# EPS_Interface.net
KiCad netlist of a schematic drawn in Altium Designer
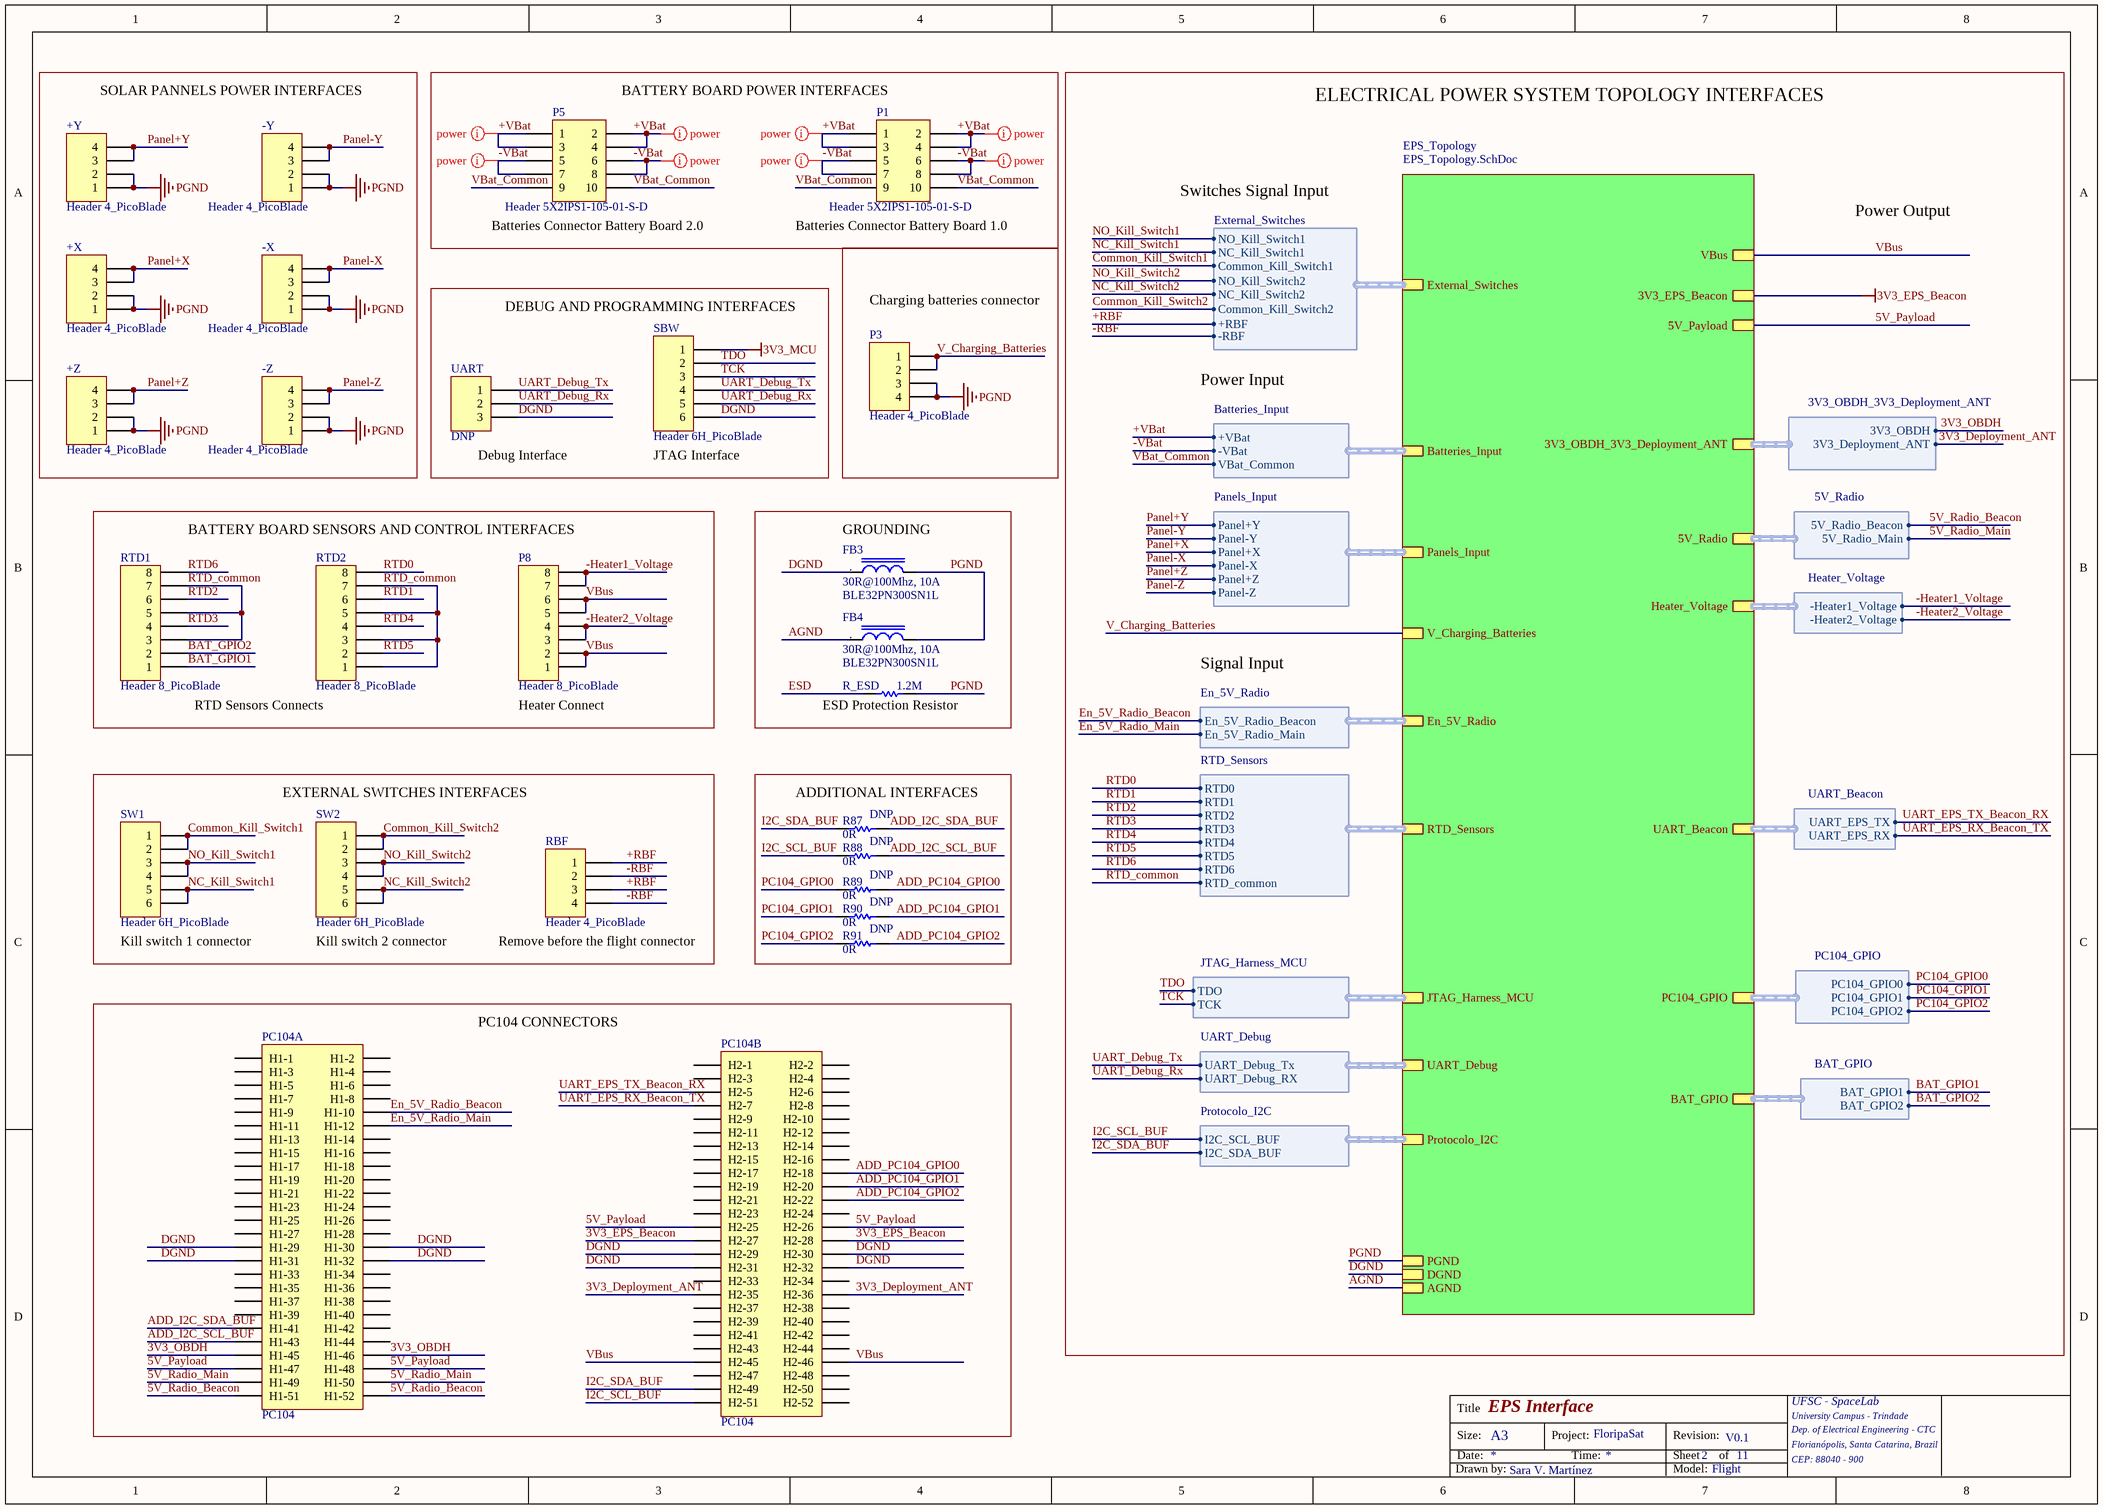
[diagram p0: EPS_Interface.SchDoc]

(export (version "E")
  (design (tool "Eeschema 10.0.6"))
  (components
    (comp (ref "+X")
      (value "Header 4_PicoBlade")
      (footprint "HDR4 PicoBlade")
      (description "Header, 4-Pin")
      (fields
        (field (name "PARTNUMBER") "53398-0471")
        (field (name "MANUFACTURER") "Molex")
        (field (name "PUBLISHER") "Altium Limited")
      )
      (libsource (lib "PCB_Project_FlightModel_EPS") (part "Header 4_PicoBlade"))
    )
    (comp (ref "+Y")
      (value "Header 4_PicoBlade")
      (footprint "HDR4 PicoBlade")
      (description "Header, 4-Pin")
      (fields
        (field (name "PARTNUMBER") "53398-0471")
        (field (name "MANUFACTURER") "Molex")
        (field (name "PUBLISHER") "Altium Limited")
      )
      (libsource (lib "PCB_Project_FlightModel_EPS") (part "Header 4_PicoBlade"))
    )
    (comp (ref "+Z")
      (value "Header 4_PicoBlade")
      (footprint "HDR4 PicoBlade")
      (description "Header, 4-Pin")
      (fields
        (field (name "PARTNUMBER") "53398-0471")
        (field (name "MANUFACTURER") "Molex")
        (field (name "PUBLISHER") "Altium Limited")
      )
      (libsource (lib "PCB_Project_FlightModel_EPS") (part "Header 4_PicoBlade"))
    )
    (comp (ref "-X")
      (value "Header 4_PicoBlade")
      (footprint "HDR4 PicoBlade")
      (description "Header, 4-Pin")
      (fields
        (field (name "PARTNUMBER") "53398-0471")
        (field (name "MANUFACTURER") "Molex")
        (field (name "PUBLISHER") "Altium Limited")
      )
      (libsource (lib "PCB_Project_FlightModel_EPS") (part "Header 4_PicoBlade"))
    )
    (comp (ref "-Y")
      (value "Header 4_PicoBlade")
      (footprint "HDR4 PicoBlade")
      (description "Header, 4-Pin")
      (fields
        (field (name "PARTNUMBER") "53398-0471")
        (field (name "MANUFACTURER") "Molex")
        (field (name "PUBLISHER") "Altium Limited")
      )
      (libsource (lib "PCB_Project_FlightModel_EPS") (part "Header 4_PicoBlade"))
    )
    (comp (ref "-Z")
      (value "Header 4_PicoBlade")
      (footprint "HDR4 PicoBlade")
      (description "Header, 4-Pin")
      (fields
        (field (name "PARTNUMBER") "53398-0471")
        (field (name "MANUFACTURER") "Molex")
        (field (name "PUBLISHER") "Altium Limited")
      )
      (libsource (lib "PCB_Project_FlightModel_EPS") (part "Header 4_PicoBlade"))
    )
    (comp (ref "FB3")
      (value "30R@100Mhz, 10A")
      (footprint "IND1210")
      (description "Ferrite Bead 30 OHM 10A 100MHz")
      (fields
        (field (name "PARTNUMBER") "BLE32PN300SN1L")
        (field (name "MANUFACTURER") "Murata")
        (field (name "MANUFACTURER PART NUMBER") "BLE32PN300SN1L")
      )
      (libsource (lib "PCB_Project_FlightModel_EPS") (part "FB_30R_10A_100MHz_1210"))
    )
    (comp (ref "FB4")
      (value "30R@100Mhz, 10A")
      (footprint "IND1210")
      (description "Ferrite Bead 30 OHM 10A 100MHz")
      (fields
        (field (name "PARTNUMBER") "BLE32PN300SN1L")
        (field (name "MANUFACTURER") "Murata")
        (field (name "MANUFACTURER PART NUMBER") "BLE32PN300SN1L")
      )
      (libsource (lib "PCB_Project_FlightModel_EPS") (part "FB_30R_10A_100MHz_1210"))
    )
    (comp (ref "P1")
      (value "Header 5X2IPS1-105-01-S-D")
      (footprint "IPS1-105-01-S-D")
      (description "10 Position Receptacle Connector 0.100\" (2.54mm)")
      (fields
        (field (name "PARTNUMBER") "IPS1-105-01-S-D")
        (field (name "MANUFACTURER") "Samtec")
        (field (name "PUBLISHER") "Altium Limited")
      )
      (libsource (lib "PCB_Project_FlightModel_EPS") (part "Header 5X2H_IPS1-105-01-S-D-VS"))
    )
    (comp (ref "P3")
      (value "Header 4_PicoBlade")
      (footprint "HDR4 PicoBlade")
      (description "Header, 4-Pin")
      (fields
        (field (name "PARTNUMBER") "53398-0471")
        (field (name "MANUFACTURER") "Molex")
        (field (name "PUBLISHER") "Altium Limited")
      )
      (libsource (lib "") (part "Header 4_PicoBlade_1"))
    )
    (comp (ref "P5")
      (value "Header 5X2IPS1-105-01-S-D")
      (footprint "IPS1-105-01-S-D")
      (description "10 Position Receptacle Connector 0.100\" (2.54mm)")
      (fields
        (field (name "PARTNUMBER") "IPS1-105-01-S-D")
        (field (name "MANUFACTURER") "Samtec")
        (field (name "PUBLISHER") "Altium Limited")
      )
      (libsource (lib "PCB_Project_FlightModel_EPS") (part "Header 5X2H_IPS1-105-01-S-D-VS"))
    )
    (comp (ref "P8")
      (value "Header 8_PicoBlade")
      (footprint "HDR8 PicoBlade")
      (description "Header, 8-Pin")
      (fields
        (field (name "PARTNUMBER") "53261-0871")
        (field (name "MANUFACTURER") "Molex")
        (field (name "PUBLISHER") "Altium Limited")
      )
      (libsource (lib "PCB_Project_FlightModel_EPS") (part "Header 8_PicoBlade"))
    )
    (comp (ref "PC104")
      (value "PC104")
      (footprint "PC104")
      (fields (field (name "PARTNUMBER") "SSW-126-01-G-D") (field (name "MANUFACTURER") "Samtec"))
      (libsource (lib "") (part "PC104_1"))
    )
    (comp (ref "R87")
      (value "0R")
      (footprint "0805")
      (description "RES 0R OHM 1/8W JUMPER 0805")
      (fields (field (name "PARTNUMBER") "CRCW08050000Z0EA") (field (name "MANUFACTURER") "Vishay"))
      (libsource (lib "PCB_Project_FlightModel_EPS") (part "R0R_JUMPER_1/8W_0805"))
    )
    (comp (ref "R88")
      (value "0R")
      (footprint "0805")
      (description "RES 0R OHM 1/8W JUMPER 0805")
      (fields (field (name "PARTNUMBER") "CRCW08050000Z0EA") (field (name "MANUFACTURER") "Vishay"))
      (libsource (lib "PCB_Project_FlightModel_EPS") (part "R0R_JUMPER_1/8W_0805"))
    )
    (comp (ref "R89")
      (value "0R")
      (footprint "0805")
      (description "RES 0R OHM 1/8W JUMPER 0805")
      (fields (field (name "PARTNUMBER") "CRCW08050000Z0EA") (field (name "MANUFACTURER") "Vishay"))
      (libsource (lib "PCB_Project_FlightModel_EPS") (part "R0R_JUMPER_1/8W_0805"))
    )
    (comp (ref "R90")
      (value "0R")
      (footprint "0805")
      (description "RES 0R OHM 1/8W JUMPER 0805")
      (fields (field (name "PARTNUMBER") "CRCW08050000Z0EA") (field (name "MANUFACTURER") "Vishay"))
      (libsource (lib "PCB_Project_FlightModel_EPS") (part "R0R_JUMPER_1/8W_0805"))
    )
    (comp (ref "R91")
      (value "0R")
      (footprint "0805")
      (description "RES 0R OHM 1/8W JUMPER 0805")
      (fields (field (name "PARTNUMBER") "CRCW08050000Z0EA") (field (name "MANUFACTURER") "Vishay"))
      (libsource (lib "PCB_Project_FlightModel_EPS") (part "R0R_JUMPER_1/8W_0805"))
    )
    (comp (ref "RBF")
      (value "Header 4_PicoBlade")
      (footprint "HDR4 PicoBlade")
      (description "Header, 4-Pin")
      (fields
        (field (name "PARTNUMBER") "53398-0471")
        (field (name "MANUFACTURER") "Molex")
        (field (name "PUBLISHER") "Altium Limited")
      )
      (libsource (lib "") (part "Header 4_PicoBlade_1"))
    )
    (comp (ref "RTD1")
      (value "Header 8_PicoBlade")
      (footprint "HDR8 PicoBlade")
      (description "Header, 8-Pin")
      (fields
        (field (name "PARTNUMBER") "53261-0871")
        (field (name "MANUFACTURER") "Molex")
        (field (name "PUBLISHER") "Altium Limited")
      )
      (libsource (lib "PCB_Project_FlightModel_EPS") (part "Header 8_PicoBlade"))
    )
    (comp (ref "RTD2")
      (value "Header 8_PicoBlade")
      (footprint "HDR8 PicoBlade")
      (description "Header, 8-Pin")
      (fields
        (field (name "PARTNUMBER") "53261-0871")
        (field (name "MANUFACTURER") "Molex")
        (field (name "PUBLISHER") "Altium Limited")
      )
      (libsource (lib "PCB_Project_FlightModel_EPS") (part "Header 8_PicoBlade"))
    )
    (comp (ref "R_ESD")
      (value "1.2M")
      (footprint "0805")
      (description "RES 1200K OHM 1/8W 0.1% 0805")
      (fields (field (name "PARTNUMBER") "RG2012P-125-B-T5") (field (name "MANUFACTURER") "Susumu"))
      (libsource (lib "PCB_Project_FlightModel_EPS") (part "R1200k_1%_1/8W_0805"))
    )
    (comp (ref "SBW")
      (value "Header 6H_PicoBlade")
      (footprint "HDR6 PicoBlade")
      (description "Header, 6-Pin, Right Angle")
      (fields
        (field (name "PARTNUMBER") "53398-0671")
        (field (name "MANUFACTURER") "Molex")
        (field (name "PUBLISHER") "Altium Limited")
      )
      (libsource (lib "PCB_Project_FlightModel_EPS") (part "Header 6H_PicoBlade"))
    )
    (comp (ref "SW1")
      (value "Header 6H_PicoBlade")
      (footprint "HDR6 PicoBlade")
      (description "Header, 6-Pin, Right Angle")
      (fields
        (field (name "PARTNUMBER") "53398-0671")
        (field (name "MANUFACTURER") "Molex")
        (field (name "PUBLISHER") "Altium Limited")
      )
      (libsource (lib "PCB_Project_FlightModel_EPS") (part "Header 6H_PicoBlade"))
    )
    (comp (ref "SW2")
      (value "Header 6H_PicoBlade")
      (footprint "HDR6 PicoBlade")
      (description "Header, 6-Pin, Right Angle")
      (fields
        (field (name "PARTNUMBER") "53398-0671")
        (field (name "MANUFACTURER") "Molex")
        (field (name "PUBLISHER") "Altium Limited")
      )
      (libsource (lib "PCB_Project_FlightModel_EPS") (part "Header 6H_PicoBlade"))
    )
    (comp (ref "UART")
      (value "DNP")
      (footprint "HDR 1X3")
      (description "Header, 3-Pin, Right Angle")
      (fields
        (field (name "PARTNUMBER") "4-103327-5")
        (field (name "MANUFACTURER") "TE Connectivity AMP")
        (field (name "PUBLISHER") "Altium Limited")
      )
      (libsource (lib "PCB_Project_FlightModel_EPS") (part "Header 3H"))
    )
  )
  (nets
    (net (code "15") (name "/+RBF") (class "Default")
      (node (ref "RBF") (pin "1") (pinfunction "1_1") (pintype "passive"))
      (node (ref "RBF") (pin "3") (pinfunction "3_3") (pintype "passive"))
    )
    (net (code "16") (name "/+VBat") (class "Default")
      (node (ref "P1") (pin "1") (pinfunction "1_1") (pintype "passive"))
      (node (ref "P1") (pin "2") (pinfunction "2_2") (pintype "passive"))
      (node (ref "P1") (pin "3") (pinfunction "3_3") (pintype "passive"))
      (node (ref "P1") (pin "4") (pinfunction "4_4") (pintype "passive"))
      (node (ref "P5") (pin "1") (pinfunction "1_1") (pintype "passive"))
      (node (ref "P5") (pin "2") (pinfunction "2_2") (pintype "passive"))
      (node (ref "P5") (pin "3") (pinfunction "3_3") (pintype "passive"))
      (node (ref "P5") (pin "4") (pinfunction "4_4") (pintype "passive"))
    )
    (net (code "17") (name "/-Heater1_Voltage") (class "Default")
      (node (ref "P8") (pin "7") (pinfunction "7_7") (pintype "passive"))
      (node (ref "P8") (pin "8") (pinfunction "8_8") (pintype "passive"))
    )
    (net (code "18") (name "/-Heater2_Voltage") (class "Default")
      (node (ref "P8") (pin "3") (pinfunction "3_3") (pintype "passive"))
      (node (ref "P8") (pin "4") (pinfunction "4_4") (pintype "passive"))
    )
    (net (code "19") (name "/-RBF") (class "Default")
      (node (ref "RBF") (pin "2") (pinfunction "2_2") (pintype "passive"))
      (node (ref "RBF") (pin "4") (pinfunction "4_4") (pintype "passive"))
    )
    (net (code "20") (name "/-VBat") (class "Default")
      (node (ref "P1") (pin "5") (pinfunction "5_5") (pintype "passive"))
      (node (ref "P1") (pin "6") (pinfunction "6_6") (pintype "passive"))
      (node (ref "P1") (pin "7") (pinfunction "7_7") (pintype "passive"))
      (node (ref "P1") (pin "8") (pinfunction "8_8") (pintype "passive"))
      (node (ref "P5") (pin "5") (pinfunction "5_5") (pintype "passive"))
      (node (ref "P5") (pin "6") (pinfunction "6_6") (pintype "passive"))
      (node (ref "P5") (pin "7") (pinfunction "7_7") (pintype "passive"))
      (node (ref "P5") (pin "8") (pinfunction "8_8") (pintype "passive"))
    )
    (net (code "21") (name "/3V3_Deployment_ANT") (class "Default")
      (node (ref "PC104") (pin "H2-35") (pinfunction "H2-35_H2-35") (pintype "passive"))
      (node (ref "PC104") (pin "H2-36") (pinfunction "H2-36_H2-36") (pintype "passive"))
    )
    (net (code "22") (name "/3V3_OBDH") (class "Default")
      (node (ref "PC104") (pin "H1-45") (pinfunction "H1-45_H1-45") (pintype "passive"))
      (node (ref "PC104") (pin "H1-46") (pinfunction "H1-46_H1-46") (pintype "passive"))
    )
    (net (code "23") (name "/5V_Payload") (class "Default")
      (node (ref "PC104") (pin "H1-47") (pinfunction "H1-47_H1-47") (pintype "passive"))
      (node (ref "PC104") (pin "H1-48") (pinfunction "H1-48_H1-48") (pintype "passive"))
      (node (ref "PC104") (pin "H2-25") (pinfunction "H2-25_H2-25") (pintype "passive"))
      (node (ref "PC104") (pin "H2-26") (pinfunction "H2-26_H2-26") (pintype "passive"))
    )
    (net (code "24") (name "/5V_Radio_Beacon") (class "Default")
      (node (ref "PC104") (pin "H1-51") (pinfunction "H1-51_H1-51") (pintype "passive"))
      (node (ref "PC104") (pin "H1-52") (pinfunction "H1-52_H1-52") (pintype "passive"))
    )
    (net (code "25") (name "/5V_Radio_Main") (class "Default")
      (node (ref "PC104") (pin "H1-49") (pinfunction "H1-49_H1-49") (pintype "passive"))
      (node (ref "PC104") (pin "H1-50") (pinfunction "H1-50_H1-50") (pintype "passive"))
    )
    (net (code "26") (name "/ADD_I2C_SCL_BUF") (class "Default")
      (node (ref "PC104") (pin "H1-43") (pinfunction "H1-43_H1-43") (pintype "passive"))
      (node (ref "R88") (pin "1") (pinfunction "1_1") (pintype "passive"))
    )
    (net (code "27") (name "/ADD_I2C_SDA_BUF") (class "Default")
      (node (ref "PC104") (pin "H1-41") (pinfunction "H1-41_H1-41") (pintype "passive"))
      (node (ref "R87") (pin "1") (pinfunction "1_1") (pintype "passive"))
    )
    (net (code "28") (name "/ADD_PC104_GPIO0") (class "Default")
      (node (ref "PC104") (pin "H2-18") (pinfunction "H2-18_H2-18") (pintype "passive"))
      (node (ref "R89") (pin "1") (pinfunction "1_1") (pintype "passive"))
    )
    (net (code "29") (name "/ADD_PC104_GPIO1") (class "Default")
      (node (ref "PC104") (pin "H2-20") (pinfunction "H2-20_H2-20") (pintype "passive"))
      (node (ref "R90") (pin "1") (pinfunction "1_1") (pintype "passive"))
    )
    (net (code "30") (name "/ADD_PC104_GPIO2") (class "Default")
      (node (ref "PC104") (pin "H2-22") (pinfunction "H2-22_H2-22") (pintype "passive"))
      (node (ref "R91") (pin "1") (pinfunction "1_1") (pintype "passive"))
    )
    (net (code "31") (name "/AGND") (class "Default")
      (node (ref "FB4") (pin "1") (pinfunction "1_1") (pintype "passive"))
    )
    (net (code "32") (name "/BAT_GPIO1") (class "Default")
      (node (ref "RTD1") (pin "1") (pinfunction "1_1") (pintype "passive"))
    )
    (net (code "33") (name "/BAT_GPIO2") (class "Default")
      (node (ref "RTD1") (pin "2") (pinfunction "2_2") (pintype "passive"))
    )
    (net (code "34") (name "/Common_Kill_Switch1") (class "Default")
      (node (ref "SW1") (pin "1") (pinfunction "1_1") (pintype "passive"))
      (node (ref "SW1") (pin "2") (pinfunction "2_2") (pintype "passive"))
    )
    (net (code "35") (name "/Common_Kill_Switch2") (class "Default")
      (node (ref "SW2") (pin "1") (pinfunction "1_1") (pintype "passive"))
      (node (ref "SW2") (pin "2") (pinfunction "2_2") (pintype "passive"))
    )
    (net (code "36") (name "/DGND") (class "Default")
      (node (ref "FB3") (pin "1") (pinfunction "1_1") (pintype "passive"))
      (node (ref "PC104") (pin "H1-29") (pinfunction "H1-29_H1-29") (pintype "passive"))
      (node (ref "PC104") (pin "H1-30") (pinfunction "H1-30_H1-30") (pintype "passive"))
      (node (ref "PC104") (pin "H1-31") (pinfunction "H1-31_H1-31") (pintype "passive"))
      (node (ref "PC104") (pin "H1-32") (pinfunction "H1-32_H1-32") (pintype "passive"))
      (node (ref "PC104") (pin "H2-29") (pinfunction "H2-29_H2-29") (pintype "passive"))
      (node (ref "PC104") (pin "H2-30") (pinfunction "H2-30_H2-30") (pintype "passive"))
      (node (ref "PC104") (pin "H2-31") (pinfunction "H2-31_H2-31") (pintype "passive"))
      (node (ref "PC104") (pin "H2-32") (pinfunction "H2-32_H2-32") (pintype "passive"))
      (node (ref "SBW") (pin "6") (pinfunction "6_6") (pintype "passive"))
      (node (ref "UART") (pin "3") (pinfunction "3_3") (pintype "passive"))
    )
    (net (code "37") (name "/ESD") (class "Default")
      (node (ref "R_ESD") (pin "2") (pinfunction "2_2") (pintype "passive"))
    )
    (net (code "38") (name "/En_5V_Radio_Beacon") (class "Default")
      (node (ref "PC104") (pin "H1-10") (pinfunction "H1-10_H1-10") (pintype "passive"))
    )
    (net (code "39") (name "/En_5V_Radio_Main") (class "Default")
      (node (ref "PC104") (pin "H1-12") (pinfunction "H1-12_H1-12") (pintype "passive"))
    )
    (net (code "40") (name "/I2C_SCL_BUF") (class "Default")
      (node (ref "PC104") (pin "H2-51") (pinfunction "H2-51_H2-51") (pintype "passive"))
      (node (ref "R88") (pin "2") (pinfunction "2_2") (pintype "passive"))
    )
    (net (code "41") (name "/I2C_SDA_BUF") (class "Default")
      (node (ref "PC104") (pin "H2-49") (pinfunction "H2-49_H2-49") (pintype "passive"))
      (node (ref "R87") (pin "2") (pinfunction "2_2") (pintype "passive"))
    )
    (net (code "42") (name "/NC_Kill_Switch1") (class "Default")
      (node (ref "SW1") (pin "5") (pinfunction "5_5") (pintype "passive"))
      (node (ref "SW1") (pin "6") (pinfunction "6_6") (pintype "passive"))
    )
    (net (code "43") (name "/NC_Kill_Switch2") (class "Default")
      (node (ref "SW2") (pin "5") (pinfunction "5_5") (pintype "passive"))
      (node (ref "SW2") (pin "6") (pinfunction "6_6") (pintype "passive"))
    )
    (net (code "44") (name "/NO_Kill_Switch1") (class "Default")
      (node (ref "SW1") (pin "3") (pinfunction "3_3") (pintype "passive"))
      (node (ref "SW1") (pin "4") (pinfunction "4_4") (pintype "passive"))
    )
    (net (code "45") (name "/NO_Kill_Switch2") (class "Default")
      (node (ref "SW2") (pin "3") (pinfunction "3_3") (pintype "passive"))
      (node (ref "SW2") (pin "4") (pinfunction "4_4") (pintype "passive"))
    )
    (net (code "46") (name "/PC104_GPIO0") (class "Default")
      (node (ref "R89") (pin "2") (pinfunction "2_2") (pintype "passive"))
    )
    (net (code "47") (name "/PC104_GPIO1") (class "Default")
      (node (ref "R90") (pin "2") (pinfunction "2_2") (pintype "passive"))
    )
    (net (code "48") (name "/PC104_GPIO2") (class "Default")
      (node (ref "R91") (pin "2") (pinfunction "2_2") (pintype "passive"))
    )
    (net (code "49") (name "/Panel+X") (class "Default")
      (node (ref "+X") (pin "3") (pinfunction "3_3") (pintype "passive"))
      (node (ref "+X") (pin "4") (pinfunction "4_4") (pintype "passive"))
    )
    (net (code "50") (name "/Panel+Y") (class "Default")
      (node (ref "+Y") (pin "3") (pinfunction "3_3") (pintype "passive"))
      (node (ref "+Y") (pin "4") (pinfunction "4_4") (pintype "passive"))
    )
    (net (code "51") (name "/Panel+Z") (class "Default")
      (node (ref "+Z") (pin "3") (pinfunction "3_3") (pintype "passive"))
      (node (ref "+Z") (pin "4") (pinfunction "4_4") (pintype "passive"))
    )
    (net (code "52") (name "/Panel-X") (class "Default")
      (node (ref "-X") (pin "3") (pinfunction "3_3") (pintype "passive"))
      (node (ref "-X") (pin "4") (pinfunction "4_4") (pintype "passive"))
    )
    (net (code "53") (name "/Panel-Y") (class "Default")
      (node (ref "-Y") (pin "3") (pinfunction "3_3") (pintype "passive"))
      (node (ref "-Y") (pin "4") (pinfunction "4_4") (pintype "passive"))
    )
    (net (code "54") (name "/Panel-Z") (class "Default")
      (node (ref "-Z") (pin "3") (pinfunction "3_3") (pintype "passive"))
      (node (ref "-Z") (pin "4") (pinfunction "4_4") (pintype "passive"))
    )
    (net (code "55") (name "/RTD0") (class "Default")
      (node (ref "RTD2") (pin "8") (pinfunction "8_8") (pintype "passive"))
    )
    (net (code "56") (name "/RTD1") (class "Default")
      (node (ref "RTD2") (pin "6") (pinfunction "6_6") (pintype "passive"))
    )
    (net (code "57") (name "/RTD2") (class "Default")
      (node (ref "RTD1") (pin "6") (pinfunction "6_6") (pintype "passive"))
    )
    (net (code "58") (name "/RTD3") (class "Default")
      (node (ref "RTD1") (pin "4") (pinfunction "4_4") (pintype "passive"))
    )
    (net (code "59") (name "/RTD4") (class "Default")
      (node (ref "RTD2") (pin "4") (pinfunction "4_4") (pintype "passive"))
    )
    (net (code "60") (name "/RTD5") (class "Default")
      (node (ref "RTD2") (pin "2") (pinfunction "2_2") (pintype "passive"))
    )
    (net (code "61") (name "/RTD6") (class "Default")
      (node (ref "RTD1") (pin "8") (pinfunction "8_8") (pintype "passive"))
    )
    (net (code "62") (name "/RTD_common") (class "Default")
      (node (ref "RTD1") (pin "3") (pinfunction "3_3") (pintype "passive"))
      (node (ref "RTD1") (pin "5") (pinfunction "5_5") (pintype "passive"))
      (node (ref "RTD1") (pin "7") (pinfunction "7_7") (pintype "passive"))
      (node (ref "RTD2") (pin "1") (pinfunction "1_1") (pintype "passive"))
      (node (ref "RTD2") (pin "3") (pinfunction "3_3") (pintype "passive"))
      (node (ref "RTD2") (pin "5") (pinfunction "5_5") (pintype "passive"))
      (node (ref "RTD2") (pin "7") (pinfunction "7_7") (pintype "passive"))
    )
    (net (code "63") (name "/TCK") (class "Default")
      (node (ref "SBW") (pin "3") (pinfunction "3_3") (pintype "passive"))
    )
    (net (code "64") (name "/TDO") (class "Default")
      (node (ref "SBW") (pin "2") (pinfunction "2_2") (pintype "passive"))
    )
    (net (code "65") (name "/UART_Debug_Rx") (class "Default")
      (node (ref "SBW") (pin "5") (pinfunction "5_5") (pintype "passive"))
      (node (ref "UART") (pin "2") (pinfunction "2_2") (pintype "passive"))
    )
    (net (code "66") (name "/UART_Debug_Tx") (class "Default")
      (node (ref "SBW") (pin "4") (pinfunction "4_4") (pintype "passive"))
      (node (ref "UART") (pin "1") (pinfunction "1_1") (pintype "passive"))
    )
    (net (code "67") (name "/UART_EPS_RX_Beacon_TX") (class "Default")
      (node (ref "PC104") (pin "H2-7") (pinfunction "H2-7_H2-7") (pintype "passive"))
    )
    (net (code "68") (name "/UART_EPS_TX_Beacon_RX") (class "Default")
      (node (ref "PC104") (pin "H2-5") (pinfunction "H2-5_H2-5") (pintype "passive"))
    )
    (net (code "69") (name "/VBat_Common") (class "Default")
      (node (ref "P1") (pin "10") (pinfunction "10_10") (pintype "passive"))
      (node (ref "P1") (pin "9") (pinfunction "9_9") (pintype "passive"))
      (node (ref "P5") (pin "10") (pinfunction "10_10") (pintype "passive"))
      (node (ref "P5") (pin "9") (pinfunction "9_9") (pintype "passive"))
    )
    (net (code "70") (name "/VBus") (class "Default")
      (node (ref "P8") (pin "1") (pinfunction "1_1") (pintype "passive"))
      (node (ref "P8") (pin "2") (pinfunction "2_2") (pintype "passive"))
      (node (ref "P8") (pin "5") (pinfunction "5_5") (pintype "passive"))
      (node (ref "P8") (pin "6") (pinfunction "6_6") (pintype "passive"))
      (node (ref "PC104") (pin "H2-45") (pinfunction "H2-45_H2-45") (pintype "passive"))
      (node (ref "PC104") (pin "H2-46") (pinfunction "H2-46_H2-46") (pintype "passive"))
    )
    (net (code "71") (name "/V_Charging_Batteries") (class "Default")
      (node (ref "P3") (pin "1") (pinfunction "1_1") (pintype "passive"))
      (node (ref "P3") (pin "2") (pinfunction "2_2") (pintype "passive"))
    )
    (net (code "86") (name "3V3_EPS_Beacon") (class "Default")
      (node (ref "PC104") (pin "H2-27") (pinfunction "H2-27_H2-27") (pintype "passive"))
      (node (ref "PC104") (pin "H2-28") (pinfunction "H2-28_H2-28") (pintype "passive"))
    )
    (net (code "87") (name "3V3_MCU") (class "Default")
      (node (ref "SBW") (pin "1") (pinfunction "1_1") (pintype "passive"))
    )
    (net (code "88") (name "PGND") (class "Default")
      (node (ref "+X") (pin "1") (pinfunction "1_1") (pintype "passive"))
      (node (ref "+X") (pin "2") (pinfunction "2_2") (pintype "passive"))
      (node (ref "+Y") (pin "1") (pinfunction "1_1") (pintype "passive"))
      (node (ref "+Y") (pin "2") (pinfunction "2_2") (pintype "passive"))
      (node (ref "+Z") (pin "1") (pinfunction "1_1") (pintype "passive"))
      (node (ref "+Z") (pin "2") (pinfunction "2_2") (pintype "passive"))
      (node (ref "-X") (pin "1") (pinfunction "1_1") (pintype "passive"))
      (node (ref "-X") (pin "2") (pinfunction "2_2") (pintype "passive"))
      (node (ref "-Y") (pin "1") (pinfunction "1_1") (pintype "passive"))
      (node (ref "-Y") (pin "2") (pinfunction "2_2") (pintype "passive"))
      (node (ref "-Z") (pin "1") (pinfunction "1_1") (pintype "passive"))
      (node (ref "-Z") (pin "2") (pinfunction "2_2") (pintype "passive"))
      (node (ref "FB3") (pin "2") (pinfunction "2_2") (pintype "passive"))
      (node (ref "FB4") (pin "2") (pinfunction "2_2") (pintype "passive"))
      (node (ref "P3") (pin "3") (pinfunction "3_3") (pintype "passive"))
      (node (ref "P3") (pin "4") (pinfunction "4_4") (pintype "passive"))
      (node (ref "R_ESD") (pin "1") (pinfunction "1_1") (pintype "passive"))
    )
    (net (code "89") (name "unconnected-(PC104-PadH1-1)") (class "Default")
      (node (ref "PC104") (pin "H1-1") (pinfunction "H1-1_H1-1") (pintype "passive"))
    )
    (net (code "90") (name "unconnected-(PC104-PadH1-2)") (class "Default")
      (node (ref "PC104") (pin "H1-2") (pinfunction "H1-2_H1-2") (pintype "passive"))
    )
    (net (code "91") (name "unconnected-(PC104-PadH1-3)") (class "Default")
      (node (ref "PC104") (pin "H1-3") (pinfunction "H1-3_H1-3") (pintype "passive"))
    )
    (net (code "92") (name "unconnected-(PC104-PadH1-4)") (class "Default")
      (node (ref "PC104") (pin "H1-4") (pinfunction "H1-4_H1-4") (pintype "passive"))
    )
    (net (code "93") (name "unconnected-(PC104-PadH1-5)") (class "Default")
      (node (ref "PC104") (pin "H1-5") (pinfunction "H1-5_H1-5") (pintype "passive"))
    )
    (net (code "94") (name "unconnected-(PC104-PadH1-6)") (class "Default")
      (node (ref "PC104") (pin "H1-6") (pinfunction "H1-6_H1-6") (pintype "passive"))
    )
    (net (code "95") (name "unconnected-(PC104-PadH1-7)") (class "Default")
      (node (ref "PC104") (pin "H1-7") (pinfunction "H1-7_H1-7") (pintype "passive"))
    )
    (net (code "96") (name "unconnected-(PC104-PadH1-8)") (class "Default")
      (node (ref "PC104") (pin "H1-8") (pinfunction "H1-8_H1-8") (pintype "passive"))
    )
    (net (code "97") (name "unconnected-(PC104-PadH1-9)") (class "Default")
      (node (ref "PC104") (pin "H1-9") (pinfunction "H1-9_H1-9") (pintype "passive"))
    )
    (net (code "98") (name "unconnected-(PC104-PadH1-11)") (class "Default")
      (node (ref "PC104") (pin "H1-11") (pinfunction "H1-11_H1-11") (pintype "passive"))
    )
    (net (code "99") (name "unconnected-(PC104-PadH1-13)") (class "Default")
      (node (ref "PC104") (pin "H1-13") (pinfunction "H1-13_H1-13") (pintype "passive"))
    )
    (net (code "100") (name "unconnected-(PC104-PadH1-14)") (class "Default")
      (node (ref "PC104") (pin "H1-14") (pinfunction "H1-14_H1-14") (pintype "passive"))
    )
    (net (code "101") (name "unconnected-(PC104-PadH1-15)") (class "Default")
      (node (ref "PC104") (pin "H1-15") (pinfunction "H1-15_H1-15") (pintype "passive"))
    )
    (net (code "102") (name "unconnected-(PC104-PadH1-16)") (class "Default")
      (node (ref "PC104") (pin "H1-16") (pinfunction "H1-16_H1-16") (pintype "passive"))
    )
    (net (code "103") (name "unconnected-(PC104-PadH1-17)") (class "Default")
      (node (ref "PC104") (pin "H1-17") (pinfunction "H1-17_H1-17") (pintype "passive"))
    )
    (net (code "104") (name "unconnected-(PC104-PadH1-18)") (class "Default")
      (node (ref "PC104") (pin "H1-18") (pinfunction "H1-18_H1-18") (pintype "passive"))
    )
    (net (code "105") (name "unconnected-(PC104-PadH1-19)") (class "Default")
      (node (ref "PC104") (pin "H1-19") (pinfunction "H1-19_H1-19") (pintype "passive"))
    )
    (net (code "106") (name "unconnected-(PC104-PadH1-20)") (class "Default")
      (node (ref "PC104") (pin "H1-20") (pinfunction "H1-20_H1-20") (pintype "passive"))
    )
    (net (code "107") (name "unconnected-(PC104-PadH1-21)") (class "Default")
      (node (ref "PC104") (pin "H1-21") (pinfunction "H1-21_H1-21") (pintype "passive"))
    )
    (net (code "108") (name "unconnected-(PC104-PadH1-22)") (class "Default")
      (node (ref "PC104") (pin "H1-22") (pinfunction "H1-22_H1-22") (pintype "passive"))
    )
    (net (code "109") (name "unconnected-(PC104-PadH1-23)") (class "Default")
      (node (ref "PC104") (pin "H1-23") (pinfunction "H1-23_H1-23") (pintype "passive"))
    )
    (net (code "110") (name "unconnected-(PC104-PadH1-24)") (class "Default")
      (node (ref "PC104") (pin "H1-24") (pinfunction "H1-24_H1-24") (pintype "passive"))
    )
    (net (code "111") (name "unconnected-(PC104-PadH1-25)") (class "Default")
      (node (ref "PC104") (pin "H1-25") (pinfunction "H1-25_H1-25") (pintype "passive"))
    )
    (net (code "112") (name "unconnected-(PC104-PadH1-26)") (class "Default")
      (node (ref "PC104") (pin "H1-26") (pinfunction "H1-26_H1-26") (pintype "passive"))
    )
    (net (code "113") (name "unconnected-(PC104-PadH1-27)") (class "Default")
      (node (ref "PC104") (pin "H1-27") (pinfunction "H1-27_H1-27") (pintype "passive"))
    )
    (net (code "114") (name "unconnected-(PC104-PadH1-28)") (class "Default")
      (node (ref "PC104") (pin "H1-28") (pinfunction "H1-28_H1-28") (pintype "passive"))
    )
    (net (code "115") (name "unconnected-(PC104-PadH1-33)") (class "Default")
      (node (ref "PC104") (pin "H1-33") (pinfunction "H1-33_H1-33") (pintype "passive"))
    )
    (net (code "116") (name "unconnected-(PC104-PadH1-34)") (class "Default")
      (node (ref "PC104") (pin "H1-34") (pinfunction "H1-34_H1-34") (pintype "passive"))
    )
    (net (code "117") (name "unconnected-(PC104-PadH1-35)") (class "Default")
      (node (ref "PC104") (pin "H1-35") (pinfunction "H1-35_H1-35") (pintype "passive"))
    )
    (net (code "118") (name "unconnected-(PC104-PadH1-36)") (class "Default")
      (node (ref "PC104") (pin "H1-36") (pinfunction "H1-36_H1-36") (pintype "passive"))
    )
    (net (code "119") (name "unconnected-(PC104-PadH1-37)") (class "Default")
      (node (ref "PC104") (pin "H1-37") (pinfunction "H1-37_H1-37") (pintype "passive"))
    )
    (net (code "120") (name "unconnected-(PC104-PadH1-38)") (class "Default")
      (node (ref "PC104") (pin "H1-38") (pinfunction "H1-38_H1-38") (pintype "passive"))
    )
    (net (code "121") (name "unconnected-(PC104-PadH1-39)") (class "Default")
      (node (ref "PC104") (pin "H1-39") (pinfunction "H1-39_H1-39") (pintype "passive"))
    )
    (net (code "122") (name "unconnected-(PC104-PadH1-40)") (class "Default")
      (node (ref "PC104") (pin "H1-40") (pinfunction "H1-40_H1-40") (pintype "passive"))
    )
    (net (code "123") (name "unconnected-(PC104-PadH1-42)") (class "Default")
      (node (ref "PC104") (pin "H1-42") (pinfunction "H1-42_H1-42") (pintype "passive"))
    )
    (net (code "124") (name "unconnected-(PC104-PadH1-44)") (class "Default")
      (node (ref "PC104") (pin "H1-44") (pinfunction "H1-44_H1-44") (pintype "passive"))
    )
    (net (code "125") (name "unconnected-(PC104-PadH2-1)") (class "Default")
      (node (ref "PC104") (pin "H2-1") (pinfunction "H2-1_H2-1") (pintype "passive"))
    )
    (net (code "126") (name "unconnected-(PC104-PadH2-2)") (class "Default")
      (node (ref "PC104") (pin "H2-2") (pinfunction "H2-2_H2-2") (pintype "passive"))
    )
    (net (code "127") (name "unconnected-(PC104-PadH2-3)") (class "Default")
      (node (ref "PC104") (pin "H2-3") (pinfunction "H2-3_H2-3") (pintype "passive"))
    )
    (net (code "128") (name "unconnected-(PC104-PadH2-4)") (class "Default")
      (node (ref "PC104") (pin "H2-4") (pinfunction "H2-4_H2-4") (pintype "passive"))
    )
    (net (code "129") (name "unconnected-(PC104-PadH2-6)") (class "Default")
      (node (ref "PC104") (pin "H2-6") (pinfunction "H2-6_H2-6") (pintype "passive"))
    )
    (net (code "130") (name "unconnected-(PC104-PadH2-8)") (class "Default")
      (node (ref "PC104") (pin "H2-8") (pinfunction "H2-8_H2-8") (pintype "passive"))
    )
    (net (code "131") (name "unconnected-(PC104-PadH2-9)") (class "Default")
      (node (ref "PC104") (pin "H2-9") (pinfunction "H2-9_H2-9") (pintype "passive"))
    )
    (net (code "132") (name "unconnected-(PC104-PadH2-10)") (class "Default")
      (node (ref "PC104") (pin "H2-10") (pinfunction "H2-10_H2-10") (pintype "passive"))
    )
    (net (code "133") (name "unconnected-(PC104-PadH2-11)") (class "Default")
      (node (ref "PC104") (pin "H2-11") (pinfunction "H2-11_H2-11") (pintype "passive"))
    )
    (net (code "134") (name "unconnected-(PC104-PadH2-12)") (class "Default")
      (node (ref "PC104") (pin "H2-12") (pinfunction "H2-12_H2-12") (pintype "passive"))
    )
    (net (code "135") (name "unconnected-(PC104-PadH2-13)") (class "Default")
      (node (ref "PC104") (pin "H2-13") (pinfunction "H2-13_H2-13") (pintype "passive"))
    )
    (net (code "136") (name "unconnected-(PC104-PadH2-14)") (class "Default")
      (node (ref "PC104") (pin "H2-14") (pinfunction "H2-14_H2-14") (pintype "passive"))
    )
    (net (code "137") (name "unconnected-(PC104-PadH2-15)") (class "Default")
      (node (ref "PC104") (pin "H2-15") (pinfunction "H2-15_H2-15") (pintype "passive"))
    )
    (net (code "138") (name "unconnected-(PC104-PadH2-16)") (class "Default")
      (node (ref "PC104") (pin "H2-16") (pinfunction "H2-16_H2-16") (pintype "passive"))
    )
    (net (code "139") (name "unconnected-(PC104-PadH2-17)") (class "Default")
      (node (ref "PC104") (pin "H2-17") (pinfunction "H2-17_H2-17") (pintype "passive"))
    )
    (net (code "140") (name "unconnected-(PC104-PadH2-19)") (class "Default")
      (node (ref "PC104") (pin "H2-19") (pinfunction "H2-19_H2-19") (pintype "passive"))
    )
    (net (code "141") (name "unconnected-(PC104-PadH2-21)") (class "Default")
      (node (ref "PC104") (pin "H2-21") (pinfunction "H2-21_H2-21") (pintype "passive"))
    )
    (net (code "142") (name "unconnected-(PC104-PadH2-23)") (class "Default")
      (node (ref "PC104") (pin "H2-23") (pinfunction "H2-23_H2-23") (pintype "passive"))
    )
    (net (code "143") (name "unconnected-(PC104-PadH2-24)") (class "Default")
      (node (ref "PC104") (pin "H2-24") (pinfunction "H2-24_H2-24") (pintype "passive"))
    )
    (net (code "144") (name "unconnected-(PC104-PadH2-33)") (class "Default")
      (node (ref "PC104") (pin "H2-33") (pinfunction "H2-33_H2-33") (pintype "passive"))
    )
    (net (code "145") (name "unconnected-(PC104-PadH2-34)") (class "Default")
      (node (ref "PC104") (pin "H2-34") (pinfunction "H2-34_H2-34") (pintype "passive"))
    )
    (net (code "146") (name "unconnected-(PC104-PadH2-37)") (class "Default")
      (node (ref "PC104") (pin "H2-37") (pinfunction "H2-37_H2-37") (pintype "passive"))
    )
    (net (code "147") (name "unconnected-(PC104-PadH2-38)") (class "Default")
      (node (ref "PC104") (pin "H2-38") (pinfunction "H2-38_H2-38") (pintype "passive"))
    )
    (net (code "148") (name "unconnected-(PC104-PadH2-39)") (class "Default")
      (node (ref "PC104") (pin "H2-39") (pinfunction "H2-39_H2-39") (pintype "passive"))
    )
    (net (code "149") (name "unconnected-(PC104-PadH2-40)") (class "Default")
      (node (ref "PC104") (pin "H2-40") (pinfunction "H2-40_H2-40") (pintype "passive"))
    )
    (net (code "150") (name "unconnected-(PC104-PadH2-41)") (class "Default")
      (node (ref "PC104") (pin "H2-41") (pinfunction "H2-41_H2-41") (pintype "passive"))
    )
    (net (code "151") (name "unconnected-(PC104-PadH2-42)") (class "Default")
      (node (ref "PC104") (pin "H2-42") (pinfunction "H2-42_H2-42") (pintype "passive"))
    )
    (net (code "152") (name "unconnected-(PC104-PadH2-43)") (class "Default")
      (node (ref "PC104") (pin "H2-43") (pinfunction "H2-43_H2-43") (pintype "passive"))
    )
    (net (code "153") (name "unconnected-(PC104-PadH2-44)") (class "Default")
      (node (ref "PC104") (pin "H2-44") (pinfunction "H2-44_H2-44") (pintype "passive"))
    )
    (net (code "154") (name "unconnected-(PC104-PadH2-47)") (class "Default")
      (node (ref "PC104") (pin "H2-47") (pinfunction "H2-47_H2-47") (pintype "passive"))
    )
    (net (code "155") (name "unconnected-(PC104-PadH2-48)") (class "Default")
      (node (ref "PC104") (pin "H2-48") (pinfunction "H2-48_H2-48") (pintype "passive"))
    )
    (net (code "156") (name "unconnected-(PC104-PadH2-50)") (class "Default")
      (node (ref "PC104") (pin "H2-50") (pinfunction "H2-50_H2-50") (pintype "passive"))
    )
    (net (code "157") (name "unconnected-(PC104B-H2-52-PadH1-52)") (class "Default")
      (node (ref "PC104") (pin "H1-52") (pinfunction "H2-52_H1-52") (pintype "passive"))
    )
  )
)
